# ESP32.net
KiCad netlist of a schematic drawn in Altium Designer
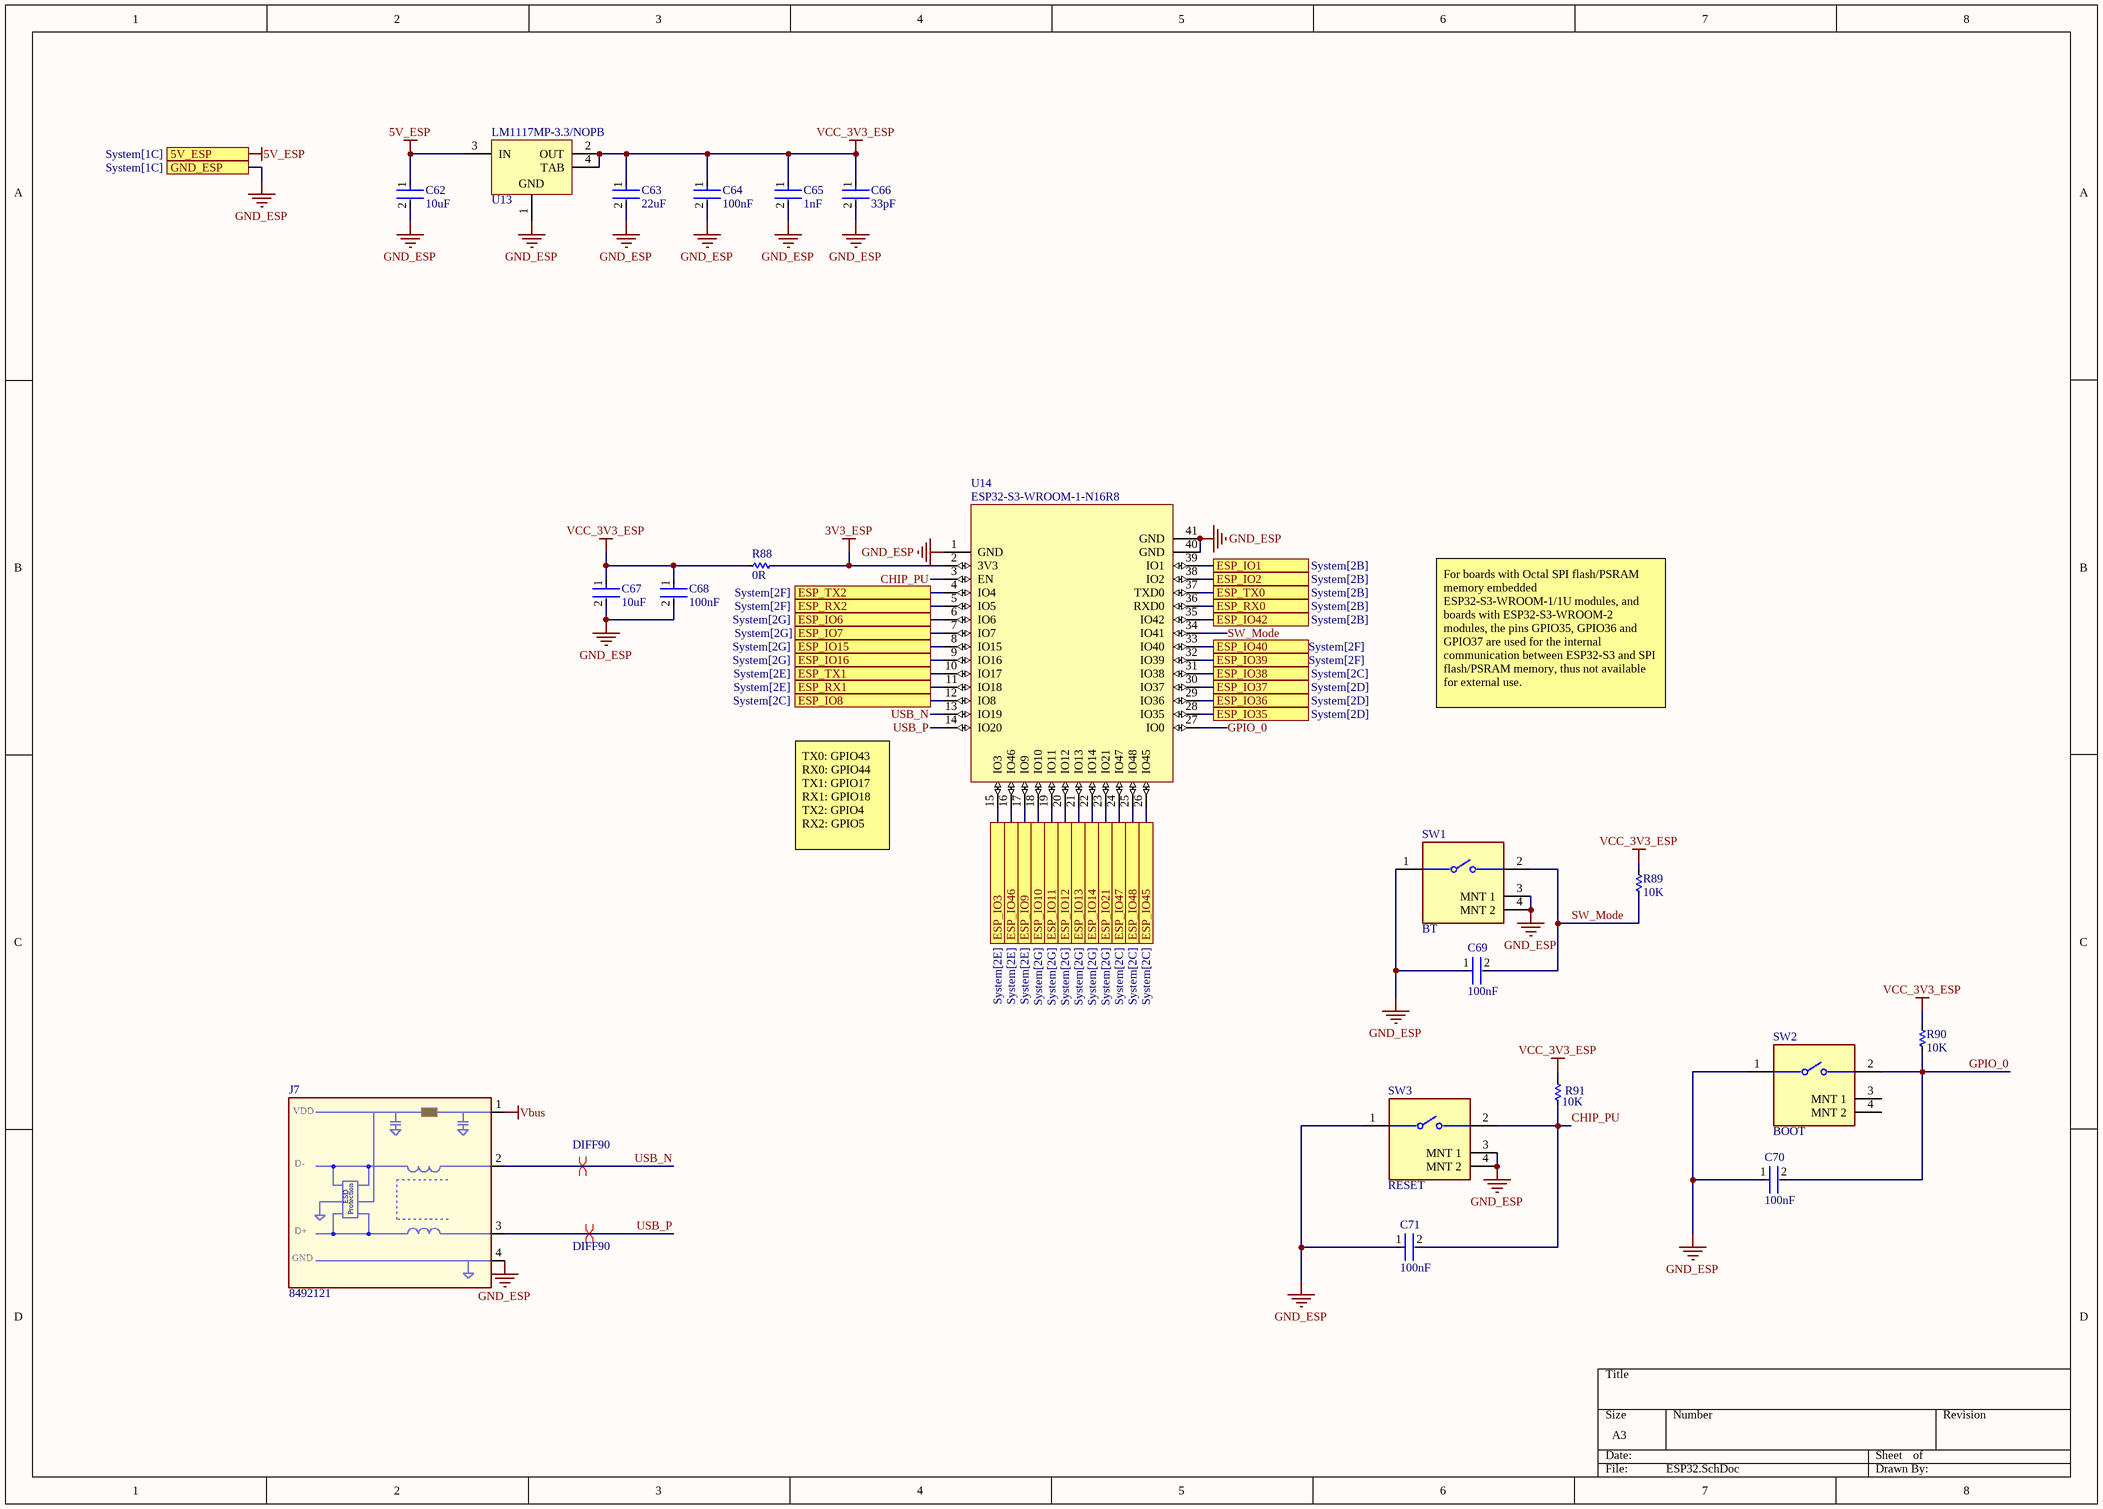
[diagram p0: ESP32.SchDoc]

(export (version "E")
  (design (tool "Eeschema 10.0.6"))
  (components
    (comp (ref "C62")
      (value "10uF")
      (footprint "FP-GRM188-0_1-e0_2_0_55-IPC_A")
      (description "Chip Multilayer Ceramic Capacitors for General Purpose, 0603")
      (fields (field (name "VOLTAGE") "6.3V") (field (name "TOLERANCE") "20%"))
      (libsource (lib "Altium Content Vault") (part "02cd4be3c70576c341d710602a673aa"))
    )
    (comp (ref "C63")
      (value "22uF")
      (footprint "FP-GRM188-0_1-e0_2_0_55-IPC_A")
      (description "Chip Multilayer Ceramic Capacitors for General Purpose, 0603")
      (fields (field (name "VOLTAGE") "6.3V") (field (name "TOLERANCE") "20%"))
      (libsource (lib "Altium Content Vault") (part "02cd4be3c70576c341d710602a673aa"))
    )
    (comp (ref "C64")
      (value "100nF")
      (footprint "FP-GRM188-0_1-e0_2_0_55-IPC_A")
      (description "Chip Multilayer Ceramic Capacitors for General Purpose, 0603")
      (fields (field (name "VOLTAGE") "6.3V") (field (name "TOLERANCE") "20%"))
      (libsource (lib "Altium Content Vault") (part "02cd4be3c70576c341d710602a673aa"))
    )
    (comp (ref "C65")
      (value "1nF")
      (footprint "FP-GRM188-0_1-e0_2_0_55-IPC_A")
      (description "Chip Multilayer Ceramic Capacitors for General Purpose, 0603")
      (fields (field (name "VOLTAGE") "6.3V") (field (name "TOLERANCE") "20%"))
      (libsource (lib "Altium Content Vault") (part "02cd4be3c70576c341d710602a673aa"))
    )
    (comp (ref "C66")
      (value "33pF")
      (footprint "FP-GRM188-0_1-e0_2_0_55-IPC_A")
      (description "Chip Multilayer Ceramic Capacitors for General Purpose, 0603")
      (fields (field (name "VOLTAGE") "6.3V") (field (name "TOLERANCE") "20%"))
      (libsource (lib "Altium Content Vault") (part "02cd4be3c70576c341d710602a673aa"))
    )
    (comp (ref "C67")
      (value "10uF")
      (footprint "FP-GRM188-0_1-e0_2_0_55-IPC_A")
      (description "Chip Multilayer Ceramic Capacitors for General Purpose, 0603")
      (fields (field (name "VOLTAGE") "6.3V") (field (name "TOLERANCE") "20%"))
      (libsource (lib "Altium Content Vault") (part "02cd4be3c70576c341d710602a673aa"))
    )
    (comp (ref "C68")
      (value "100nF")
      (footprint "FP-GRM188-0_1-e0_2_0_55-IPC_A")
      (description "Chip Multilayer Ceramic Capacitors for General Purpose, 0603")
      (fields (field (name "VOLTAGE") "6.3V") (field (name "TOLERANCE") "20%"))
      (libsource (lib "Altium Content Vault") (part "02cd4be3c70576c341d710602a673aa"))
    )
    (comp (ref "C69")
      (value "100nF")
      (footprint "FP-GRM188-0_1-e0_2_0_55-IPC_A")
      (description "Chip Multilayer Ceramic Capacitors for General Purpose, 0603")
      (fields (field (name "VOLTAGE") "6.3V") (field (name "TOLERANCE") "20%"))
      (libsource (lib "Altium Content Vault") (part "02cd4be3c70576c341d710602a673aa"))
    )
    (comp (ref "C70")
      (value "100nF")
      (footprint "FP-CGA3E-0_3-0_1-IPC_A")
      (description "Cap Ceramic 100nF 50V X7R 10% Pad SMD 0603 +125°C Automotive T/R")
      (fields (field (name "TOLERANCE") "10%") (field (name "VOLTAGE") "50V"))
      (libsource (lib "Altium Content Vault") (part "b4654b650e69147ec39a6b967a45e02"))
    )
    (comp (ref "C71")
      (value "100nF")
      (footprint "FP-CGA3E-0_3-0_1-IPC_A")
      (description "Cap Ceramic 100nF 50V X7R 10% Pad SMD 0603 +125°C Automotive T/R")
      (fields (field (name "TOLERANCE") "10%") (field (name "VOLTAGE") "50V"))
      (libsource (lib "Altium Content Vault") (part "b4654b650e69147ec39a6b967a45e02"))
    )
    (comp (ref "J7")
      (value "8492121")
      (footprint "USB-C2")
      (description "THT USB 2.0 A Connector WE-EPLE")
      (fields
        (field (name "MANUFACTURER") "Würth Elektronik eiSos GmbH")
        (field (name "CREATED BY") "Christin Otto")
      )
      (libsource (lib "TechMT.VN_Lib_Project v2") (part "USB-4"))
    )
    (comp (ref "R88")
      (value "0R")
      (footprint "RES-SMD-0603")
      (description "Resistor 0603")
      (fields
        (field (name "MANUFACTURER") "Generic Components")
        (field (name "PUBLISHER") "Altium Hobart Technology Centre")
      )
      (libsource (lib "TechMT.VN_Lib_Project v2") (part "Res-SMD"))
    )
    (comp (ref "R89")
      (value "10K")
      (footprint "RES-SMD-0603")
      (description "Resistor 0603")
      (fields
        (field (name "MANUFACTURER") "Generic Components")
        (field (name "PUBLISHER") "Altium Hobart Technology Centre")
      )
      (libsource (lib "TechMT.VN_Lib_Project v2") (part "Res-SMD"))
    )
    (comp (ref "R90")
      (value "10K")
      (footprint "RES-SMD-0603")
      (description "Resistor 0603")
      (fields
        (field (name "MANUFACTURER") "Generic Components")
        (field (name "PUBLISHER") "Altium Hobart Technology Centre")
      )
      (libsource (lib "TechMT.VN_Lib_Project v2") (part "Res-SMD"))
    )
    (comp (ref "R91")
      (value "10K")
      (footprint "RES-SMD-0603")
      (description "Resistor 0603")
      (fields
        (field (name "MANUFACTURER") "Generic Components")
        (field (name "PUBLISHER") "Altium Hobart Technology Centre")
      )
      (libsource (lib "TechMT.VN_Lib_Project v2") (part "Res-SMD"))
    )
    (comp (ref "SW1")
      (value "BT")
      (footprint "FP-1825027-8-MFG")
      (description "SWITCH TACTILE SPST-NO 0.05A 24V")
      (fields
        (field (name "MANUFACTURER") "TE Connectivity")
        (field (name "OCTOPART") "https://octopart.com/1825027-8-te+connectivity-41891101")
      )
      (libsource (lib "Altium Content Vault") (part "710c863c6dfdf6196cc88dcf85d5a08"))
    )
    (comp (ref "SW2")
      (value "BOOT")
      (footprint "FP-1825027-8-MFG")
      (description "SWITCH TACTILE SPST-NO 0.05A 24V")
      (fields
        (field (name "MANUFACTURER") "TE Connectivity")
        (field (name "OCTOPART") "https://octopart.com/1825027-8-te+connectivity-41891101")
      )
      (libsource (lib "Altium Content Vault") (part "710c863c6dfdf6196cc88dcf85d5a08"))
    )
    (comp (ref "SW3")
      (value "RESET")
      (footprint "FP-1825027-8-MFG")
      (description "SWITCH TACTILE SPST-NO 0.05A 24V")
      (fields
        (field (name "MANUFACTURER") "TE Connectivity")
        (field (name "OCTOPART") "https://octopart.com/1825027-8-te+connectivity-41891101")
      )
      (libsource (lib "Altium Content Vault") (part "710c863c6dfdf6196cc88dcf85d5a08"))
    )
    (comp (ref "U13")
      (value "LM1117MP-3.3/NOPB")
      (footprint "DCY0004A_M")
      (description "800mA Low-Dropout Linear Regulator, 4-pin SOT-223, Pb-Free")
      (fields (field (name "MANUFACTURER") "Texas Instruments"))
      (libsource (lib "Altium Content Vault") (part "PM-REG-LM1086-SOT4"))
    )
    (comp (ref "U14")
      (value "ESP32-S3-WROOM-1-N16R8")
      (footprint "ESP32S3WROOM1N8R2")
      (description "Bluetooth, WiFi 802.11b/g/n, Bluetooth v5.0 Transceiver Module 2.4GHz PCB Trace Surface Mount")
      (fields (field (name "MF") "Espressif Systems"))
      (libsource (lib "Lib_NHN") (part "ESP32-S3-WROOM-1-N16R8"))
    )
  )
  (nets
    (net (code "1") (name "/CHIP_PU") (class "Default")
      (node (ref "C71") (pin "2") (pinfunction "2_2") (pintype "passive"))
      (node (ref "R91") (pin "1") (pinfunction "1_1") (pintype "passive"))
      (node (ref "SW3") (pin "2") (pinfunction "2_2") (pintype "passive"))
      (node (ref "U14") (pin "3") (pinfunction "EN_3") (pintype "bidirectional"))
    )
    (net (code "2") (name "/ESP_IO1") (class "Default")
      (node (ref "U14") (pin "39") (pinfunction "IO1_39") (pintype "bidirectional"))
    )
    (net (code "3") (name "/ESP_IO2") (class "Default")
      (node (ref "U14") (pin "38") (pinfunction "IO2_38") (pintype "bidirectional"))
    )
    (net (code "4") (name "/ESP_IO3") (class "Default")
      (node (ref "U14") (pin "15") (pinfunction "IO3_15") (pintype "bidirectional"))
    )
    (net (code "5") (name "/ESP_IO6") (class "Default")
      (node (ref "U14") (pin "6") (pinfunction "IO6_6") (pintype "bidirectional"))
    )
    (net (code "6") (name "/ESP_IO7") (class "Default")
      (node (ref "U14") (pin "7") (pinfunction "IO7_7") (pintype "bidirectional"))
    )
    (net (code "7") (name "/ESP_IO8") (class "Default")
      (node (ref "U14") (pin "12") (pinfunction "IO8_12") (pintype "bidirectional"))
    )
    (net (code "8") (name "/ESP_IO9") (class "Default")
      (node (ref "U14") (pin "17") (pinfunction "IO9_17") (pintype "bidirectional"))
    )
    (net (code "9") (name "/ESP_IO10") (class "Default")
      (node (ref "U14") (pin "18") (pinfunction "IO10_18") (pintype "bidirectional"))
    )
    (net (code "10") (name "/ESP_IO11") (class "Default")
      (node (ref "U14") (pin "19") (pinfunction "IO11_19") (pintype "bidirectional"))
    )
    (net (code "11") (name "/ESP_IO12") (class "Default")
      (node (ref "U14") (pin "20") (pinfunction "IO12_20") (pintype "bidirectional"))
    )
    (net (code "12") (name "/ESP_IO13") (class "Default")
      (node (ref "U14") (pin "21") (pinfunction "IO13_21") (pintype "bidirectional"))
    )
    (net (code "13") (name "/ESP_IO14") (class "Default")
      (node (ref "U14") (pin "22") (pinfunction "IO14_22") (pintype "bidirectional"))
    )
    (net (code "14") (name "/ESP_IO15") (class "Default")
      (node (ref "U14") (pin "8") (pinfunction "IO15_8") (pintype "bidirectional"))
    )
    (net (code "15") (name "/ESP_IO16") (class "Default")
      (node (ref "U14") (pin "9") (pinfunction "IO16_9") (pintype "bidirectional"))
    )
    (net (code "16") (name "/ESP_IO21") (class "Default")
      (node (ref "U14") (pin "23") (pinfunction "IO21_23") (pintype "bidirectional"))
    )
    (net (code "17") (name "/ESP_IO35") (class "Default")
      (node (ref "U14") (pin "28") (pinfunction "IO35_28") (pintype "bidirectional"))
    )
    (net (code "18") (name "/ESP_IO36") (class "Default")
      (node (ref "U14") (pin "29") (pinfunction "IO36_29") (pintype "bidirectional"))
    )
    (net (code "19") (name "/ESP_IO37") (class "Default")
      (node (ref "U14") (pin "30") (pinfunction "IO37_30") (pintype "bidirectional"))
    )
    (net (code "20") (name "/ESP_IO38") (class "Default")
      (node (ref "U14") (pin "31") (pinfunction "IO38_31") (pintype "bidirectional"))
    )
    (net (code "21") (name "/ESP_IO39") (class "Default")
      (node (ref "U14") (pin "32") (pinfunction "IO39_32") (pintype "bidirectional"))
    )
    (net (code "22") (name "/ESP_IO40") (class "Default")
      (node (ref "U14") (pin "33") (pinfunction "IO40_33") (pintype "bidirectional"))
    )
    (net (code "23") (name "/ESP_IO42") (class "Default")
      (node (ref "U14") (pin "35") (pinfunction "IO42_35") (pintype "bidirectional"))
    )
    (net (code "24") (name "/ESP_IO45") (class "Default")
      (node (ref "U14") (pin "26") (pinfunction "IO45_26") (pintype "bidirectional"))
    )
    (net (code "25") (name "/ESP_IO46") (class "Default")
      (node (ref "U14") (pin "16") (pinfunction "IO46_16") (pintype "bidirectional"))
    )
    (net (code "26") (name "/ESP_IO47") (class "Default")
      (node (ref "U14") (pin "24") (pinfunction "IO47_24") (pintype "bidirectional"))
    )
    (net (code "27") (name "/ESP_IO48") (class "Default")
      (node (ref "U14") (pin "25") (pinfunction "IO48_25") (pintype "bidirectional"))
    )
    (net (code "28") (name "/ESP_RX0") (class "Default")
      (node (ref "U14") (pin "36") (pinfunction "RXD0_36") (pintype "bidirectional"))
    )
    (net (code "29") (name "/ESP_RX1") (class "Default")
      (node (ref "U14") (pin "11") (pinfunction "IO18_11") (pintype "bidirectional"))
    )
    (net (code "30") (name "/ESP_RX2") (class "Default")
      (node (ref "U14") (pin "5") (pinfunction "IO5_5") (pintype "bidirectional"))
    )
    (net (code "31") (name "/ESP_TX0") (class "Default")
      (node (ref "U14") (pin "37") (pinfunction "TXD0_37") (pintype "bidirectional"))
    )
    (net (code "32") (name "/ESP_TX1") (class "Default")
      (node (ref "U14") (pin "10") (pinfunction "IO17_10") (pintype "bidirectional"))
    )
    (net (code "33") (name "/ESP_TX2") (class "Default")
      (node (ref "U14") (pin "4") (pinfunction "IO4_4") (pintype "bidirectional"))
    )
    (net (code "34") (name "/GPIO_0") (class "Default")
      (node (ref "C70") (pin "2") (pinfunction "2_2") (pintype "passive"))
      (node (ref "R90") (pin "1") (pinfunction "1_1") (pintype "passive"))
      (node (ref "SW2") (pin "2") (pinfunction "2_2") (pintype "passive"))
      (node (ref "U14") (pin "27") (pinfunction "IO0_27") (pintype "bidirectional"))
    )
    (net (code "35") (name "/SW_Mode") (class "Default")
      (node (ref "C69") (pin "2") (pinfunction "2_2") (pintype "passive"))
      (node (ref "R89") (pin "1") (pinfunction "1_1") (pintype "passive"))
      (node (ref "SW1") (pin "2") (pinfunction "2_2") (pintype "passive"))
      (node (ref "U14") (pin "34") (pinfunction "IO41_34") (pintype "bidirectional"))
    )
    (net (code "36") (name "/USB_N") (class "Default")
      (node (ref "J7") (pin "2") (pinfunction "D-_2") (pintype "passive"))
      (node (ref "U14") (pin "13") (pinfunction "IO19_13") (pintype "bidirectional"))
    )
    (net (code "37") (name "/USB_P") (class "Default")
      (node (ref "J7") (pin "3") (pinfunction "D+_3") (pintype "passive"))
      (node (ref "U14") (pin "14") (pinfunction "IO20_14") (pintype "bidirectional"))
    )
    (net (code "38") (name "3V3_ESP") (class "Default")
      (node (ref "R88") (pin "1") (pinfunction "1_1") (pintype "passive"))
      (node (ref "U14") (pin "2") (pinfunction "3V3_2") (pintype "bidirectional"))
    )
    (net (code "39") (name "5V_ESP") (class "Default")
      (node (ref "C62") (pin "1") (pinfunction "1_1") (pintype "passive"))
      (node (ref "U13") (pin "3") (pinfunction "IN_3") (pintype "power_in"))
    )
    (net (code "40") (name "GND_ESP") (class "Default")
      (node (ref "C62") (pin "2") (pinfunction "2_2") (pintype "passive"))
      (node (ref "C63") (pin "2") (pinfunction "2_2") (pintype "passive"))
      (node (ref "C64") (pin "2") (pinfunction "2_2") (pintype "passive"))
      (node (ref "C65") (pin "2") (pinfunction "2_2") (pintype "passive"))
      (node (ref "C66") (pin "2") (pinfunction "2_2") (pintype "passive"))
      (node (ref "C67") (pin "2") (pinfunction "2_2") (pintype "passive"))
      (node (ref "C68") (pin "2") (pinfunction "2_2") (pintype "passive"))
      (node (ref "C69") (pin "1") (pinfunction "1_1") (pintype "passive"))
      (node (ref "C70") (pin "1") (pinfunction "1_1") (pintype "passive"))
      (node (ref "C71") (pin "1") (pinfunction "1_1") (pintype "passive"))
      (node (ref "J7") (pin "4") (pinfunction "GND_4") (pintype "passive"))
      (node (ref "SW1") (pin "1") (pinfunction "1_1") (pintype "passive"))
      (node (ref "SW1") (pin "3") (pinfunction "MNT_1_3") (pintype "passive"))
      (node (ref "SW1") (pin "4") (pinfunction "MNT_2_4") (pintype "passive"))
      (node (ref "SW2") (pin "1") (pinfunction "1_1") (pintype "passive"))
      (node (ref "SW3") (pin "1") (pinfunction "1_1") (pintype "passive"))
      (node (ref "SW3") (pin "3") (pinfunction "MNT_1_3") (pintype "passive"))
      (node (ref "SW3") (pin "4") (pinfunction "MNT_2_4") (pintype "passive"))
      (node (ref "U13") (pin "1") (pinfunction "GND_1") (pintype "power_in"))
      (node (ref "U14") (pin "1") (pinfunction "GND_1") (pintype "power_in"))
      (node (ref "U14") (pin "40") (pinfunction "GND_40") (pintype "power_in"))
      (node (ref "U14") (pin "41") (pinfunction "GND_41") (pintype "power_in"))
    )
    (net (code "41") (name "VCC_3V3_ESP") (class "Default")
      (node (ref "C63") (pin "1") (pinfunction "1_1") (pintype "passive"))
      (node (ref "C64") (pin "1") (pinfunction "1_1") (pintype "passive"))
      (node (ref "C65") (pin "1") (pinfunction "1_1") (pintype "passive"))
      (node (ref "C66") (pin "1") (pinfunction "1_1") (pintype "passive"))
      (node (ref "C67") (pin "1") (pinfunction "1_1") (pintype "passive"))
      (node (ref "C68") (pin "1") (pinfunction "1_1") (pintype "passive"))
      (node (ref "R88") (pin "2") (pinfunction "2_2") (pintype "passive"))
      (node (ref "R89") (pin "2") (pinfunction "2_2") (pintype "passive"))
      (node (ref "R90") (pin "2") (pinfunction "2_2") (pintype "passive"))
      (node (ref "R91") (pin "2") (pinfunction "2_2") (pintype "passive"))
      (node (ref "U13") (pin "2") (pinfunction "OUT_2") (pintype "power_in"))
      (node (ref "U13") (pin "4") (pinfunction "TAB_4") (pintype "power_in"))
    )
    (net (code "42") (name "Vbus") (class "Default")
      (node (ref "J7") (pin "1") (pinfunction "VBUS_1") (pintype "passive"))
    )
    (net (code "43") (name "unconnected-(SW2-MNT_1-Pad3)") (class "Default")
      (node (ref "SW2") (pin "3") (pinfunction "MNT_1_3") (pintype "passive"))
    )
    (net (code "44") (name "unconnected-(SW2-MNT_2-Pad4)") (class "Default")
      (node (ref "SW2") (pin "4") (pinfunction "MNT_2_4") (pintype "passive"))
    )
  )
)
